# STM32_Shematic.net
KiCad netlist of a schematic drawn in Altium Designer
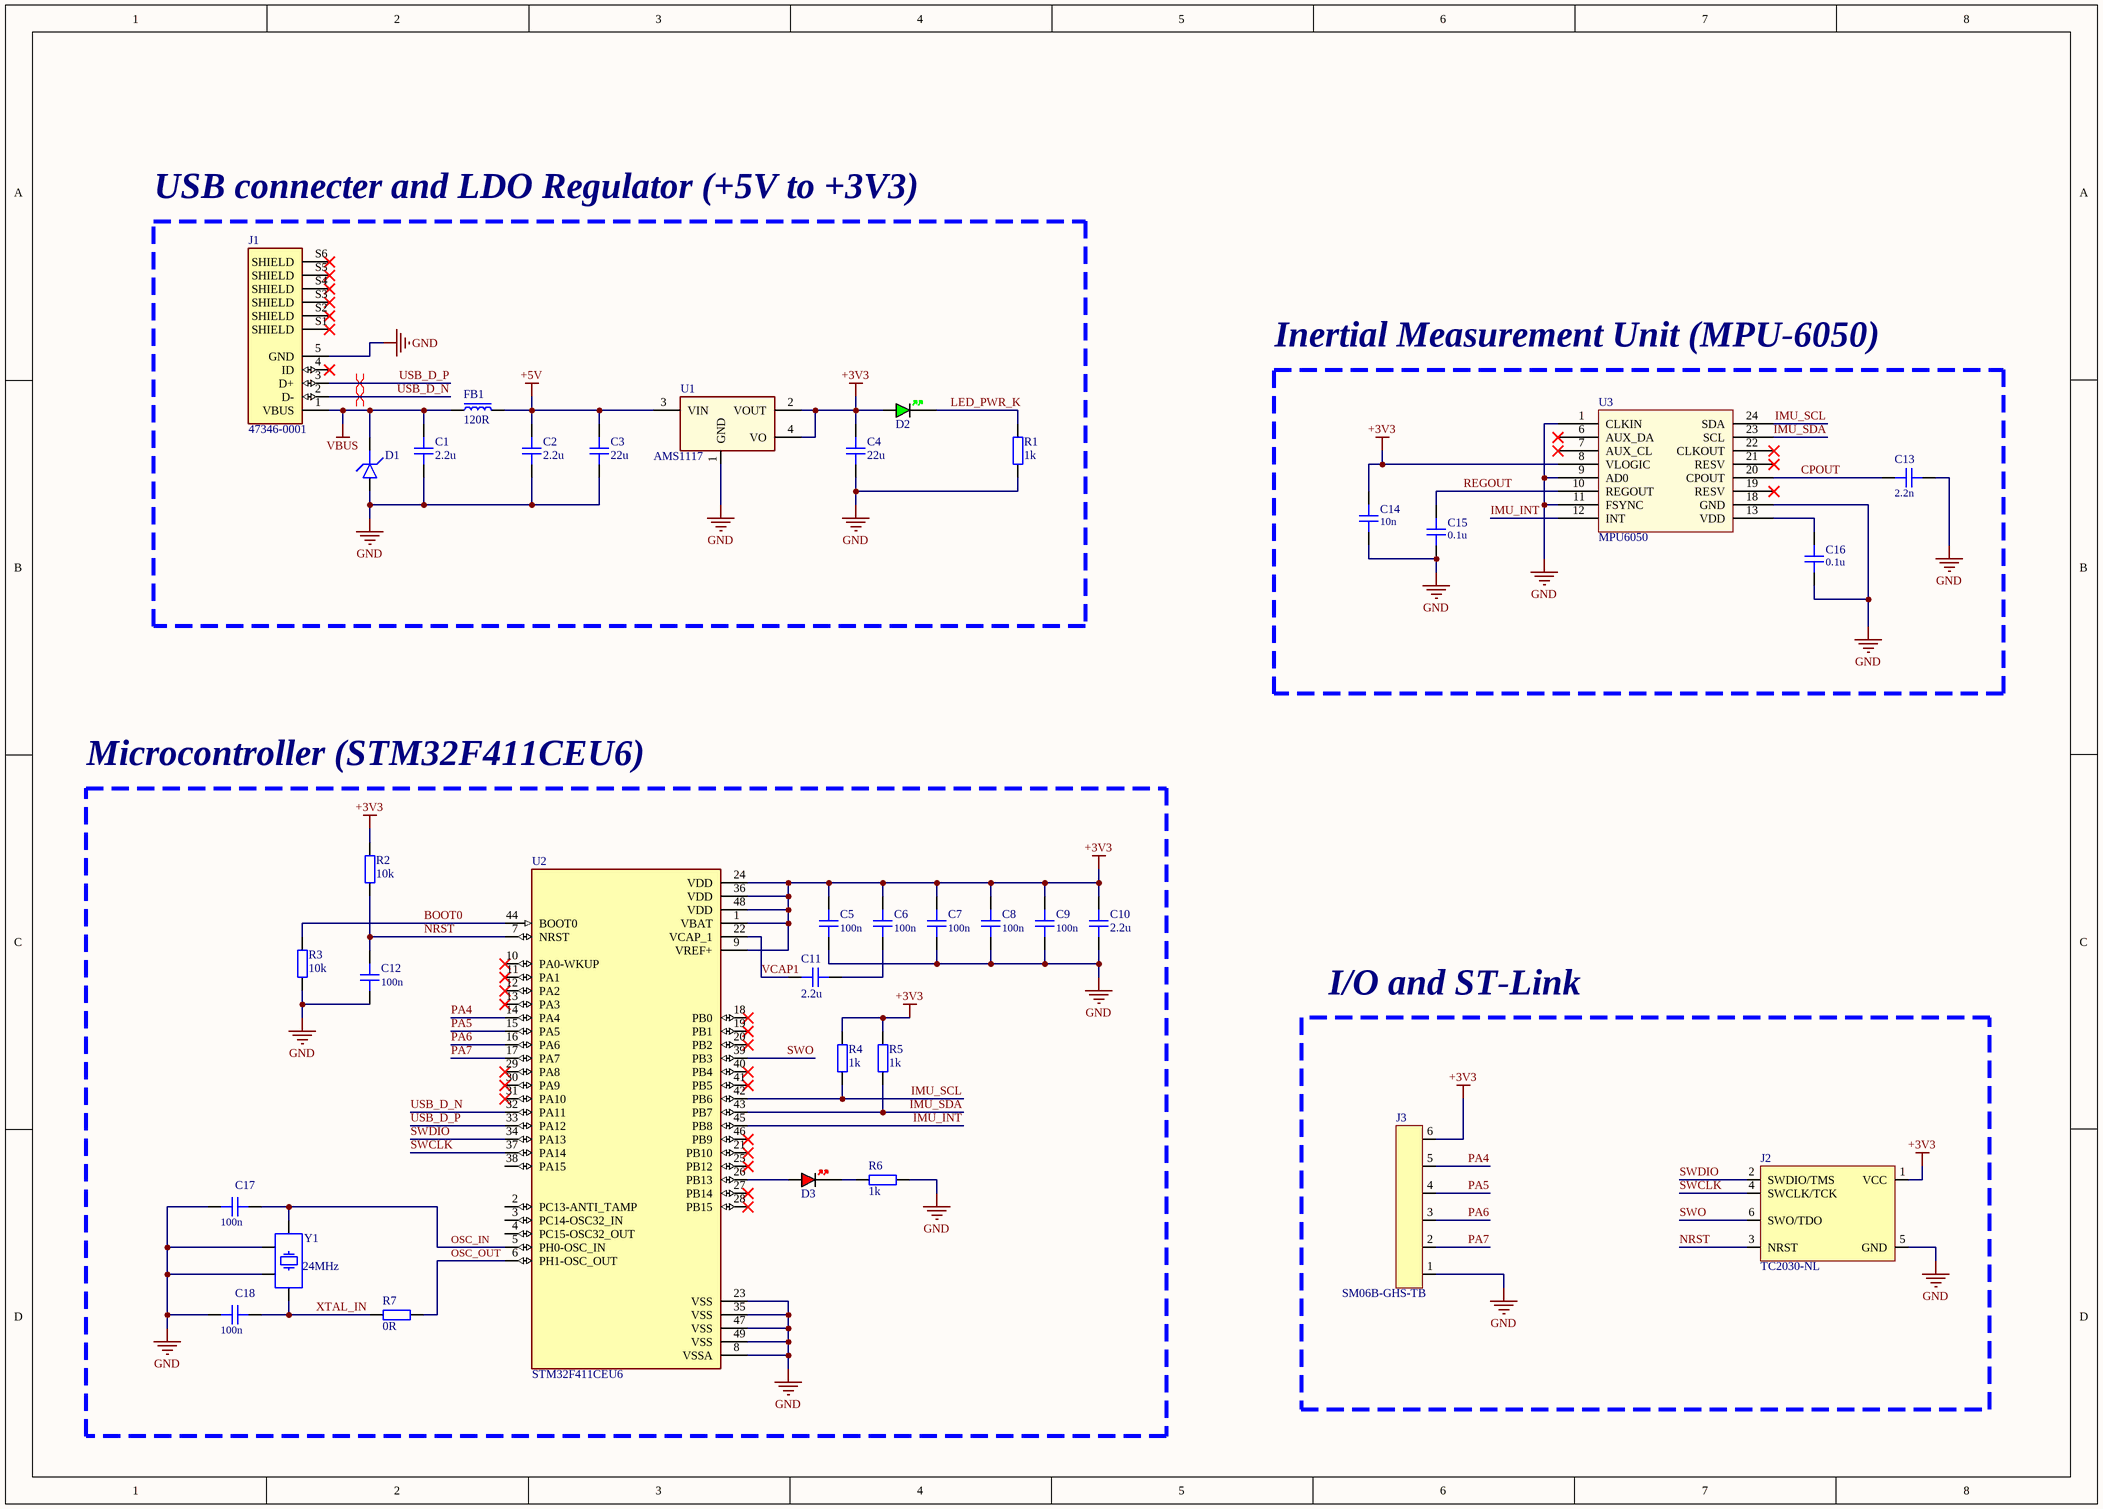
[diagram p0: STM32_Shematic.SchDoc]

(export (version "E")
  (design (tool "Eeschema 10.0.6"))
  (components
    (comp (ref "C1")
      (value "2.2u")
      (footprint "CAP_0603")
      (description "Capacitor SMD 0603 16V")
      (libsource (lib "Trong_modun") (part "CAP_0603_16V"))
    )
    (comp (ref "C2")
      (value "2.2u")
      (footprint "CAP_0603")
      (description "Capacitor SMD 0603 16V")
      (libsource (lib "Trong_modun") (part "CAP_0603_16V"))
    )
    (comp (ref "C3")
      (value "22u")
      (footprint "CAP_0805")
      (description "Capacitor SMD 0805 16V")
      (libsource (lib "Trong_modun") (part "CAP_0805_16V"))
    )
    (comp (ref "C4")
      (value "22u")
      (footprint "CAP_0805")
      (description "Capacitor SMD 0805 16V")
      (libsource (lib "Trong_modun") (part "CAP_0805_16V"))
    )
    (comp (ref "C5")
      (value "100n")
      (footprint "CAP_0402")
      (description "Capacitor SMD 0402 16V")
      (libsource (lib "Trong_modun") (part "CAP_0402_16V"))
    )
    (comp (ref "C6")
      (value "100n")
      (footprint "CAP_0402")
      (description "Capacitor SMD 0402 16V")
      (libsource (lib "Trong_modun") (part "CAP_0402_16V"))
    )
    (comp (ref "C7")
      (value "100n")
      (footprint "CAP_0402")
      (description "Capacitor SMD 0402 16V")
      (libsource (lib "Trong_modun") (part "CAP_0402_16V"))
    )
    (comp (ref "C8")
      (value "100n")
      (footprint "CAP_0402")
      (description "Capacitor SMD 0402 16V")
      (libsource (lib "Trong_modun") (part "CAP_0402_16V"))
    )
    (comp (ref "C9")
      (value "100n")
      (footprint "CAP_0402")
      (description "Capacitor SMD 0402 16V")
      (libsource (lib "Trong_modun") (part "CAP_0402_16V"))
    )
    (comp (ref "C10")
      (value "2.2u")
      (footprint "CAP_0603")
      (description "Capacitor SMD 0603 16V")
      (libsource (lib "Trong_modun") (part "CAP_0603_16V"))
    )
    (comp (ref "C11")
      (value "2.2u")
      (footprint "CAP_0603")
      (description "Capacitor SMD 0603 16V")
      (libsource (lib "Trong_modun") (part "CAP_0603_16V"))
    )
    (comp (ref "C12")
      (value "100n")
      (footprint "CAP_0402")
      (description "Capacitor SMD 0402 16V")
      (libsource (lib "Trong_modun") (part "CAP_0402_16V"))
    )
    (comp (ref "C13")
      (value "2.2n")
      (footprint "CAP_0402")
      (description "Capacitor SMD 0402 16V")
      (libsource (lib "Trong_modun") (part "CAP_0402_16V"))
    )
    (comp (ref "C14")
      (value "10n")
      (footprint "CAP_0402")
      (description "Capacitor SMD 0402 16V")
      (libsource (lib "Trong_modun") (part "CAP_0402_16V"))
    )
    (comp (ref "C15")
      (value "0.1u")
      (footprint "CAP_0402")
      (description "Capacitor SMD 0402 16V")
      (libsource (lib "Trong_modun") (part "CAP_0402_16V"))
    )
    (comp (ref "C16")
      (value "0.1u")
      (footprint "CAP_0402")
      (description "Capacitor SMD 0402 16V")
      (libsource (lib "Trong_modun") (part "CAP_0402_16V"))
    )
    (comp (ref "C17")
      (value "100n")
      (footprint "CAP_0402")
      (description "Capacitor SMD 0402 16V")
      (libsource (lib "Trong_modun") (part "CAP_0402_16V"))
    )
    (comp (ref "C18")
      (value "100n")
      (footprint "CAP_0402")
      (description "Capacitor SMD 0402 16V")
      (libsource (lib "Trong_modun") (part "CAP_0402_16V"))
    )
    (comp (ref "D1")
      (value "~")
      (footprint "D_0402")
      (description "Diode TVS / ESD 0402")
      (libsource (lib "Trong_modun") (part "D_TVS_0402"))
    )
    (comp (ref "D2")
      (value "GREEN")
      (footprint "LED_0402_GREEN")
      (description "LED 0402 GREEN SMD")
      (libsource (lib "Trong_modun") (part "LED_0402_GREEN"))
    )
    (comp (ref "D3")
      (value "RED")
      (footprint "LED_0402_RED")
      (description "LED 0402 RED SMD")
      (libsource (lib "Trong_modun") (part "LED_0402_RED"))
    )
    (comp (ref "FB1")
      (value "120R")
      (footprint "FB_0603")
      (description "Ferrite Bead SMD 0603")
      (libsource (lib "Trong_modun") (part "FB_0603"))
    )
    (comp (ref "J1")
      (value "47346-0001")
      (footprint "MOLEX_47346-0001")
      (description "Conn Data USB Micro B w/Flange SMT Bottom Mnt LF ¦ Molex Incorporated 47346-0001")
      (fields (field (name "MF") "Molex"))
      (libsource (lib "47346-0001") (part "47346-0001"))
    )
    (comp (ref "J2")
      (value "TC2030-NL")
      (footprint "TC2030-NL-FP")
      (description "Tag-Connect No-Solder SWD Debug Connector (No Legs) DO NOT PLACE")
      (fields
        (field (name "MANUFACTURER") "Tag-Connect")
        (field (name "MANUFACTURER PART NUMBER") "TC2030-NL-FP")
      )
      (libsource (lib "Trong_modun") (part "TC2030-NL"))
    )
    (comp (ref "J3")
      (value "SM06B-GHS-TB")
      (footprint "SM06B-GHS-TB")
      (description "Header Connector 6 Position 1.25MM Pitch SMD Horizontal JST GH")
      (fields (field (name "MANUFACTURER") "JST"))
      (libsource (lib "Trong_modun") (part "SM06B-GHS-TB"))
    )
    (comp (ref "R1")
      (value "1k")
      (footprint "RES_0402")
      (description "Resistor SMD 0402")
      (libsource (lib "Trong_modun") (part "RES_0402"))
    )
    (comp (ref "R2")
      (value "10k")
      (footprint "RES_0402")
      (description "Resistor SMD 0402")
      (libsource (lib "Trong_modun") (part "RES_0402"))
    )
    (comp (ref "R3")
      (value "10k")
      (footprint "RES_0402")
      (description "Resistor SMD 0402")
      (libsource (lib "Trong_modun") (part "RES_0402"))
    )
    (comp (ref "R4")
      (value "1k")
      (footprint "RES_0402")
      (description "Resistor SMD 0402")
      (libsource (lib "Trong_modun") (part "RES_0402"))
    )
    (comp (ref "R5")
      (value "1k")
      (footprint "RES_0402")
      (description "Resistor SMD 0402")
      (libsource (lib "Trong_modun") (part "RES_0402"))
    )
    (comp (ref "R6")
      (value "1k")
      (footprint "RES_0402")
      (description "Resistor SMD 0402")
      (libsource (lib "Trong_modun") (part "RES_0402"))
    )
    (comp (ref "R7")
      (value "0R")
      (footprint "RES_0402")
      (description "Resistor SMD 0402")
      (libsource (lib "Trong_modun") (part "RES_0402"))
    )
    (comp (ref "U1")
      (value "AMS1117")
      (footprint "SOT-223")
      (description "1A LDO Voltage Regulator, ADJ or fixed 1.5/1.8/2.5/2.85/3.3/5V")
      (libsource (lib "chipfc_altium_libs") (part "AMS1117"))
    )
    (comp (ref "U2")
      (value "STM32F411CEU6")
      (footprint "QFN50P700X700X60-49N")
      (libsource (lib "STM32F411CEU6") (part "STM32F411CEU6"))
    )
    (comp (ref "U3") (value "MPU6050") (libsource (lib "Cty1") (part "MPU6050")))
    (comp (ref "Y1")
      (value "24MHz")
      (footprint "XTAL_3225")
      (description "Crystal SMD 24MHz 10PPM 7pF 3225")
      (fields (field (name "MANUFACTURER") "Epson"))
      (libsource (lib "Trong_modun") (part "TSX-3225_24.0000MF15X-AC"))
    )
  )
  (nets
    (net (code "1") (name "+3V3") (class "Default")
      (node (ref "C10") (pin "2") (pinfunction "2_2") (pintype "passive"))
      (node (ref "C14") (pin "2") (pinfunction "2_2") (pintype "passive"))
      (node (ref "C4") (pin "2") (pinfunction "2_2") (pintype "passive"))
      (node (ref "C5") (pin "2") (pinfunction "2_2") (pintype "passive"))
      (node (ref "C6") (pin "2") (pinfunction "2_2") (pintype "passive"))
      (node (ref "C7") (pin "2") (pinfunction "2_2") (pintype "passive"))
      (node (ref "C8") (pin "2") (pinfunction "2_2") (pintype "passive"))
      (node (ref "C9") (pin "2") (pinfunction "2_2") (pintype "passive"))
      (node (ref "D2") (pin "A") (pinfunction "A_A") (pintype "passive"))
      (node (ref "J2") (pin "1") (pinfunction "VCC_1") (pintype "passive"))
      (node (ref "J3") (pin "6") (pinfunction "6_6") (pintype "passive"))
      (node (ref "R2") (pin "2") (pinfunction "2_2") (pintype "passive"))
      (node (ref "R4") (pin "1") (pinfunction "1_1") (pintype "passive"))
      (node (ref "R5") (pin "1") (pinfunction "1_1") (pintype "passive"))
      (node (ref "U1") (pin "2") (pinfunction "VOUT_2") (pintype "passive"))
      (node (ref "U1") (pin "4") (pinfunction "VO_4") (pintype "passive"))
      (node (ref "U2") (pin "1") (pinfunction "VBAT_1") (pintype "power_in"))
      (node (ref "U2") (pin "24") (pinfunction "VDD_24") (pintype "power_in"))
      (node (ref "U2") (pin "36") (pinfunction "VDD_36") (pintype "power_in"))
      (node (ref "U2") (pin "48") (pinfunction "VDD_48") (pintype "power_in"))
      (node (ref "U2") (pin "9") (pinfunction "VREF+_9") (pintype "power_in"))
      (node (ref "U3") (pin "8") (pinfunction "VLOGIC_8") (pintype "passive"))
    )
    (net (code "2") (name "+5V") (class "Default")
      (node (ref "C2") (pin "2") (pinfunction "2_2") (pintype "passive"))
      (node (ref "C3") (pin "2") (pinfunction "2_2") (pintype "passive"))
      (node (ref "FB1") (pin "2") (pinfunction "2_2") (pintype "passive"))
      (node (ref "U1") (pin "3") (pinfunction "VIN_3") (pintype "power_in"))
    )
    (net (code "3") (name "/BOOT0") (class "Default")
      (node (ref "R3") (pin "2") (pinfunction "2_2") (pintype "passive"))
      (node (ref "U2") (pin "44") (pinfunction "BOOT0_44") (pintype "input"))
    )
    (net (code "4") (name "/CPOUT") (class "Default")
      (node (ref "C13") (pin "1") (pinfunction "1_1") (pintype "passive"))
      (node (ref "U3") (pin "20") (pinfunction "CPOUT_20") (pintype "passive"))
    )
    (net (code "5") (name "/IMU_INT") (class "Default")
      (node (ref "U2") (pin "45") (pinfunction "PB8_45") (pintype "bidirectional"))
      (node (ref "U3") (pin "12") (pinfunction "INT_12") (pintype "passive"))
    )
    (net (code "6") (name "/IMU_SCL") (class "Default")
      (node (ref "R4") (pin "2") (pinfunction "2_2") (pintype "passive"))
      (node (ref "U2") (pin "42") (pinfunction "PB6_42") (pintype "bidirectional"))
      (node (ref "U3") (pin "24") (pinfunction "SDA_24") (pintype "passive"))
    )
    (net (code "7") (name "/IMU_SDA") (class "Default")
      (node (ref "R5") (pin "2") (pinfunction "2_2") (pintype "passive"))
      (node (ref "U2") (pin "43") (pinfunction "PB7_43") (pintype "bidirectional"))
      (node (ref "U3") (pin "23") (pinfunction "SCL_23") (pintype "passive"))
    )
    (net (code "8") (name "/LED_PWR_K") (class "Default")
      (node (ref "D2") (pin "K") (pinfunction "K_K") (pintype "passive"))
      (node (ref "R1") (pin "2") (pinfunction "2_2") (pintype "passive"))
    )
    (net (code "9") (name "/NRST") (class "Default")
      (node (ref "C12") (pin "2") (pinfunction "2_2") (pintype "passive"))
      (node (ref "J2") (pin "3") (pinfunction "NRST_3") (pintype "passive"))
      (node (ref "R2") (pin "1") (pinfunction "1_1") (pintype "passive"))
      (node (ref "U2") (pin "7") (pinfunction "NRST_7") (pintype "bidirectional"))
    )
    (net (code "10") (name "/OSC_IN") (class "Default")
      (node (ref "C17") (pin "1") (pinfunction "1_1") (pintype "passive"))
      (node (ref "U2") (pin "5") (pinfunction "PH0-OSC_IN_5") (pintype "bidirectional"))
      (node (ref "Y1") (pin "1") (pinfunction "1_1") (pintype "passive"))
    )
    (net (code "11") (name "/OSC_OUT") (class "Default")
      (node (ref "R7") (pin "1") (pinfunction "1_1") (pintype "passive"))
      (node (ref "U2") (pin "6") (pinfunction "PH1-OSC_OUT_6") (pintype "bidirectional"))
    )
    (net (code "12") (name "/PA4") (class "Default")
      (node (ref "J3") (pin "5") (pinfunction "5_5") (pintype "passive"))
      (node (ref "U2") (pin "14") (pinfunction "PA4_14") (pintype "bidirectional"))
    )
    (net (code "13") (name "/PA5") (class "Default")
      (node (ref "J3") (pin "4") (pinfunction "4_4") (pintype "passive"))
      (node (ref "U2") (pin "15") (pinfunction "PA5_15") (pintype "bidirectional"))
    )
    (net (code "14") (name "/PA6") (class "Default")
      (node (ref "J3") (pin "3") (pinfunction "3_3") (pintype "passive"))
      (node (ref "U2") (pin "16") (pinfunction "PA6_16") (pintype "bidirectional"))
    )
    (net (code "15") (name "/PA7") (class "Default")
      (node (ref "J3") (pin "2") (pinfunction "2_2") (pintype "passive"))
      (node (ref "U2") (pin "17") (pinfunction "PA7_17") (pintype "bidirectional"))
    )
    (net (code "16") (name "/REGOUT") (class "Default")
      (node (ref "C15") (pin "1") (pinfunction "1_1") (pintype "passive"))
      (node (ref "U3") (pin "10") (pinfunction "REGOUT_10") (pintype "passive"))
    )
    (net (code "17") (name "/SWCLK") (class "Default")
      (node (ref "J2") (pin "4") (pinfunction "SWCLK/TCK_4") (pintype "passive"))
      (node (ref "U2") (pin "37") (pinfunction "PA14_37") (pintype "bidirectional"))
    )
    (net (code "18") (name "/SWDIO") (class "Default")
      (node (ref "J2") (pin "2") (pinfunction "SWDIO/TMS_2") (pintype "passive"))
      (node (ref "U2") (pin "34") (pinfunction "PA13_34") (pintype "bidirectional"))
    )
    (net (code "19") (name "/SWO") (class "Default")
      (node (ref "J2") (pin "6") (pinfunction "SWO/TDO_6") (pintype "passive"))
      (node (ref "U2") (pin "39") (pinfunction "PB3_39") (pintype "bidirectional"))
    )
    (net (code "20") (name "/USB_D_N") (class "Default")
      (node (ref "J1") (pin "2") (pinfunction "D-_2") (pintype "bidirectional"))
      (node (ref "U2") (pin "32") (pinfunction "PA11_32") (pintype "bidirectional"))
    )
    (net (code "21") (name "/USB_D_P") (class "Default")
      (node (ref "J1") (pin "3") (pinfunction "D+_3") (pintype "bidirectional"))
      (node (ref "U2") (pin "33") (pinfunction "PA12_33") (pintype "bidirectional"))
    )
    (net (code "22") (name "/VCAP1") (class "Default")
      (node (ref "C11") (pin "2") (pinfunction "2_2") (pintype "passive"))
      (node (ref "U2") (pin "22") (pinfunction "VCAP_1_22") (pintype "power_in"))
    )
    (net (code "23") (name "/XTAL_IN") (class "Default")
      (node (ref "C18") (pin "1") (pinfunction "1_1") (pintype "passive"))
      (node (ref "R7") (pin "2") (pinfunction "2_2") (pintype "passive"))
      (node (ref "Y1") (pin "3") (pinfunction "3_3") (pintype "passive"))
    )
    (net (code "24") (name "GND") (class "Default")
      (node (ref "C1") (pin "1") (pinfunction "1_1") (pintype "passive"))
      (node (ref "C10") (pin "1") (pinfunction "1_1") (pintype "passive"))
      (node (ref "C12") (pin "1") (pinfunction "1_1") (pintype "passive"))
      (node (ref "C13") (pin "2") (pinfunction "2_2") (pintype "passive"))
      (node (ref "C14") (pin "1") (pinfunction "1_1") (pintype "passive"))
      (node (ref "C15") (pin "2") (pinfunction "2_2") (pintype "passive"))
      (node (ref "C16") (pin "2") (pinfunction "2_2") (pintype "passive"))
      (node (ref "C17") (pin "2") (pinfunction "2_2") (pintype "passive"))
      (node (ref "C18") (pin "2") (pinfunction "2_2") (pintype "passive"))
      (node (ref "C2") (pin "1") (pinfunction "1_1") (pintype "passive"))
      (node (ref "C3") (pin "1") (pinfunction "1_1") (pintype "passive"))
      (node (ref "C4") (pin "1") (pinfunction "1_1") (pintype "passive"))
      (node (ref "C5") (pin "1") (pinfunction "1_1") (pintype "passive"))
      (node (ref "C7") (pin "1") (pinfunction "1_1") (pintype "passive"))
      (node (ref "C8") (pin "1") (pinfunction "1_1") (pintype "passive"))
      (node (ref "C9") (pin "1") (pinfunction "1_1") (pintype "passive"))
      (node (ref "D1") (pin "A") (pinfunction "A_A") (pintype "passive"))
      (node (ref "J1") (pin "5") (pinfunction "GND_5") (pintype "power_in"))
      (node (ref "J2") (pin "5") (pinfunction "GND_5") (pintype "passive"))
      (node (ref "J3") (pin "1") (pinfunction "1_1") (pintype "passive"))
      (node (ref "R1") (pin "1") (pinfunction "1_1") (pintype "passive"))
      (node (ref "R3") (pin "1") (pinfunction "1_1") (pintype "passive"))
      (node (ref "R6") (pin "1") (pinfunction "1_1") (pintype "passive"))
      (node (ref "U1") (pin "1") (pinfunction "GND_1") (pintype "passive"))
      (node (ref "U2") (pin "23") (pinfunction "VSS_23") (pintype "power_in"))
      (node (ref "U2") (pin "35") (pinfunction "VSS_35") (pintype "power_in"))
      (node (ref "U2") (pin "47") (pinfunction "VSS_47") (pintype "power_in"))
      (node (ref "U2") (pin "49") (pinfunction "VSS_49") (pintype "power_in"))
      (node (ref "U2") (pin "8") (pinfunction "VSSA_8") (pintype "power_in"))
      (node (ref "U3") (pin "1") (pinfunction "CLKIN_1") (pintype "passive"))
      (node (ref "U3") (pin "11") (pinfunction "FSYNC_11") (pintype "passive"))
      (node (ref "U3") (pin "18") (pinfunction "GND_18") (pintype "passive"))
      (node (ref "U3") (pin "9") (pinfunction "AD0_9") (pintype "passive"))
      (node (ref "Y1") (pin "2") (pinfunction "2_2") (pintype "passive"))
      (node (ref "Y1") (pin "4") (pinfunction "4_4") (pintype "passive"))
    )
    (net (code "25") (name "Net-(C11-Pad1)") (class "Default")
      (node (ref "C11") (pin "1") (pinfunction "1_1") (pintype "passive"))
      (node (ref "C6") (pin "1") (pinfunction "1_1") (pintype "passive"))
    )
    (net (code "26") (name "Net-(D3-PadK)") (class "Default")
      (node (ref "D3") (pin "K") (pinfunction "K_K") (pintype "passive"))
      (node (ref "R6") (pin "2") (pinfunction "2_2") (pintype "passive"))
    )
    (net (code "27") (name "Net-(U2-PB13)") (class "Default")
      (node (ref "D3") (pin "A") (pinfunction "A_A") (pintype "passive"))
      (node (ref "U2") (pin "26") (pinfunction "PB13_26") (pintype "bidirectional"))
    )
    (net (code "28") (name "Net-(U3-VDD)") (class "Default")
      (node (ref "C16") (pin "1") (pinfunction "1_1") (pintype "passive"))
      (node (ref "U3") (pin "13") (pinfunction "VDD_13") (pintype "passive"))
    )
    (net (code "29") (name "VBUS") (class "Default")
      (node (ref "C1") (pin "2") (pinfunction "2_2") (pintype "passive"))
      (node (ref "D1") (pin "K") (pinfunction "K_K") (pintype "passive"))
      (node (ref "FB1") (pin "1") (pinfunction "1_1") (pintype "passive"))
      (node (ref "J1") (pin "1") (pinfunction "VBUS_1") (pintype "power_in"))
    )
    (net (code "30") (name "unconnected-(J1-ID-Pad4)") (class "Default")
      (node (ref "J1") (pin "4") (pinfunction "ID_4") (pintype "bidirectional+no_connect"))
    )
    (net (code "31") (name "unconnected-(J1-SHIELD-PadS1)") (class "Default")
      (node (ref "J1") (pin "S1") (pinfunction "SHIELD_S1") (pintype "passive+no_connect"))
    )
    (net (code "32") (name "unconnected-(J1-SHIELD-PadS2)") (class "Default")
      (node (ref "J1") (pin "S2") (pinfunction "SHIELD_S2") (pintype "passive+no_connect"))
    )
    (net (code "33") (name "unconnected-(J1-SHIELD-PadS3)") (class "Default")
      (node (ref "J1") (pin "S3") (pinfunction "SHIELD_S3") (pintype "passive+no_connect"))
    )
    (net (code "34") (name "unconnected-(J1-SHIELD-PadS4)") (class "Default")
      (node (ref "J1") (pin "S4") (pinfunction "SHIELD_S4") (pintype "passive+no_connect"))
    )
    (net (code "35") (name "unconnected-(J1-SHIELD-PadS5)") (class "Default")
      (node (ref "J1") (pin "S5") (pinfunction "SHIELD_S5") (pintype "passive+no_connect"))
    )
    (net (code "36") (name "unconnected-(J1-SHIELD-PadS6)") (class "Default")
      (node (ref "J1") (pin "S6") (pinfunction "SHIELD_S6") (pintype "passive+no_connect"))
    )
    (net (code "37") (name "unconnected-(U2-PA0-WKUP-Pad10)") (class "Default")
      (node (ref "U2") (pin "10") (pinfunction "PA0-WKUP_10") (pintype "bidirectional+no_connect"))
    )
    (net (code "38") (name "unconnected-(U2-PA1-Pad11)") (class "Default")
      (node (ref "U2") (pin "11") (pinfunction "PA1_11") (pintype "bidirectional+no_connect"))
    )
    (net (code "39") (name "unconnected-(U2-PA2-Pad12)") (class "Default")
      (node (ref "U2") (pin "12") (pinfunction "PA2_12") (pintype "bidirectional+no_connect"))
    )
    (net (code "40") (name "unconnected-(U2-PA3-Pad13)") (class "Default")
      (node (ref "U2") (pin "13") (pinfunction "PA3_13") (pintype "bidirectional+no_connect"))
    )
    (net (code "41") (name "unconnected-(U2-PA8-Pad29)") (class "Default")
      (node (ref "U2") (pin "29") (pinfunction "PA8_29") (pintype "bidirectional+no_connect"))
    )
    (net (code "42") (name "unconnected-(U2-PA9-Pad30)") (class "Default")
      (node (ref "U2") (pin "30") (pinfunction "PA9_30") (pintype "bidirectional+no_connect"))
    )
    (net (code "43") (name "unconnected-(U2-PA10-Pad31)") (class "Default")
      (node (ref "U2") (pin "31") (pinfunction "PA10_31") (pintype "bidirectional+no_connect"))
    )
    (net (code "44") (name "unconnected-(U2-PA15-Pad38)") (class "Default")
      (node (ref "U2") (pin "38") (pinfunction "PA15_38") (pintype "bidirectional"))
    )
    (net (code "45") (name "unconnected-(U2-PB0-Pad18)") (class "Default")
      (node (ref "U2") (pin "18") (pinfunction "PB0_18") (pintype "bidirectional+no_connect"))
    )
    (net (code "46") (name "unconnected-(U2-PB1-Pad19)") (class "Default")
      (node (ref "U2") (pin "19") (pinfunction "PB1_19") (pintype "bidirectional+no_connect"))
    )
    (net (code "47") (name "unconnected-(U2-PB2-Pad20)") (class "Default")
      (node (ref "U2") (pin "20") (pinfunction "PB2_20") (pintype "bidirectional+no_connect"))
    )
    (net (code "48") (name "unconnected-(U2-PB4-Pad40)") (class "Default")
      (node (ref "U2") (pin "40") (pinfunction "PB4_40") (pintype "bidirectional+no_connect"))
    )
    (net (code "49") (name "unconnected-(U2-PB5-Pad41)") (class "Default")
      (node (ref "U2") (pin "41") (pinfunction "PB5_41") (pintype "bidirectional+no_connect"))
    )
    (net (code "50") (name "unconnected-(U2-PB9-Pad46)") (class "Default")
      (node (ref "U2") (pin "46") (pinfunction "PB9_46") (pintype "bidirectional+no_connect"))
    )
    (net (code "51") (name "unconnected-(U2-PB10-Pad21)") (class "Default")
      (node (ref "U2") (pin "21") (pinfunction "PB10_21") (pintype "bidirectional+no_connect"))
    )
    (net (code "52") (name "unconnected-(U2-PB12-Pad25)") (class "Default")
      (node (ref "U2") (pin "25") (pinfunction "PB12_25") (pintype "bidirectional+no_connect"))
    )
    (net (code "53") (name "unconnected-(U2-PB14-Pad27)") (class "Default")
      (node (ref "U2") (pin "27") (pinfunction "PB14_27") (pintype "bidirectional+no_connect"))
    )
    (net (code "54") (name "unconnected-(U2-PB15-Pad28)") (class "Default")
      (node (ref "U2") (pin "28") (pinfunction "PB15_28") (pintype "bidirectional+no_connect"))
    )
    (net (code "55") (name "unconnected-(U2-PC13-ANTI_TAMP-Pad2)") (class "Default")
      (node (ref "U2") (pin "2") (pinfunction "PC13-ANTI_TAMP_2") (pintype "bidirectional"))
    )
    (net (code "56") (name "unconnected-(U2-PC14-OSC32_IN-Pad3)") (class "Default")
      (node (ref "U2") (pin "3") (pinfunction "PC14-OSC32_IN_3") (pintype "bidirectional"))
    )
    (net (code "57") (name "unconnected-(U2-PC15-OSC32_OUT-Pad4)") (class "Default")
      (node (ref "U2") (pin "4") (pinfunction "PC15-OSC32_OUT_4") (pintype "bidirectional"))
    )
    (net (code "58") (name "unconnected-(U3-AUX_CL-Pad7)") (class "Default")
      (node (ref "U3") (pin "7") (pinfunction "AUX_CL_7") (pintype "passive+no_connect"))
    )
    (net (code "59") (name "unconnected-(U3-AUX_DA-Pad6)") (class "Default")
      (node (ref "U3") (pin "6") (pinfunction "AUX_DA_6") (pintype "passive+no_connect"))
    )
    (net (code "60") (name "unconnected-(U3-CLKOUT-Pad22)") (class "Default")
      (node (ref "U3") (pin "22") (pinfunction "CLKOUT_22") (pintype "passive+no_connect"))
    )
    (net (code "61") (name "unconnected-(U3-RESV-Pad19)") (class "Default")
      (node (ref "U3") (pin "19") (pinfunction "RESV_19") (pintype "passive+no_connect"))
    )
    (net (code "62") (name "unconnected-(U3-RESV-Pad21)") (class "Default")
      (node (ref "U3") (pin "21") (pinfunction "RESV_21") (pintype "passive+no_connect"))
    )
  )
)
